# motorController-merged.net
KiCad netlist of a schematic drawn in EAGLE
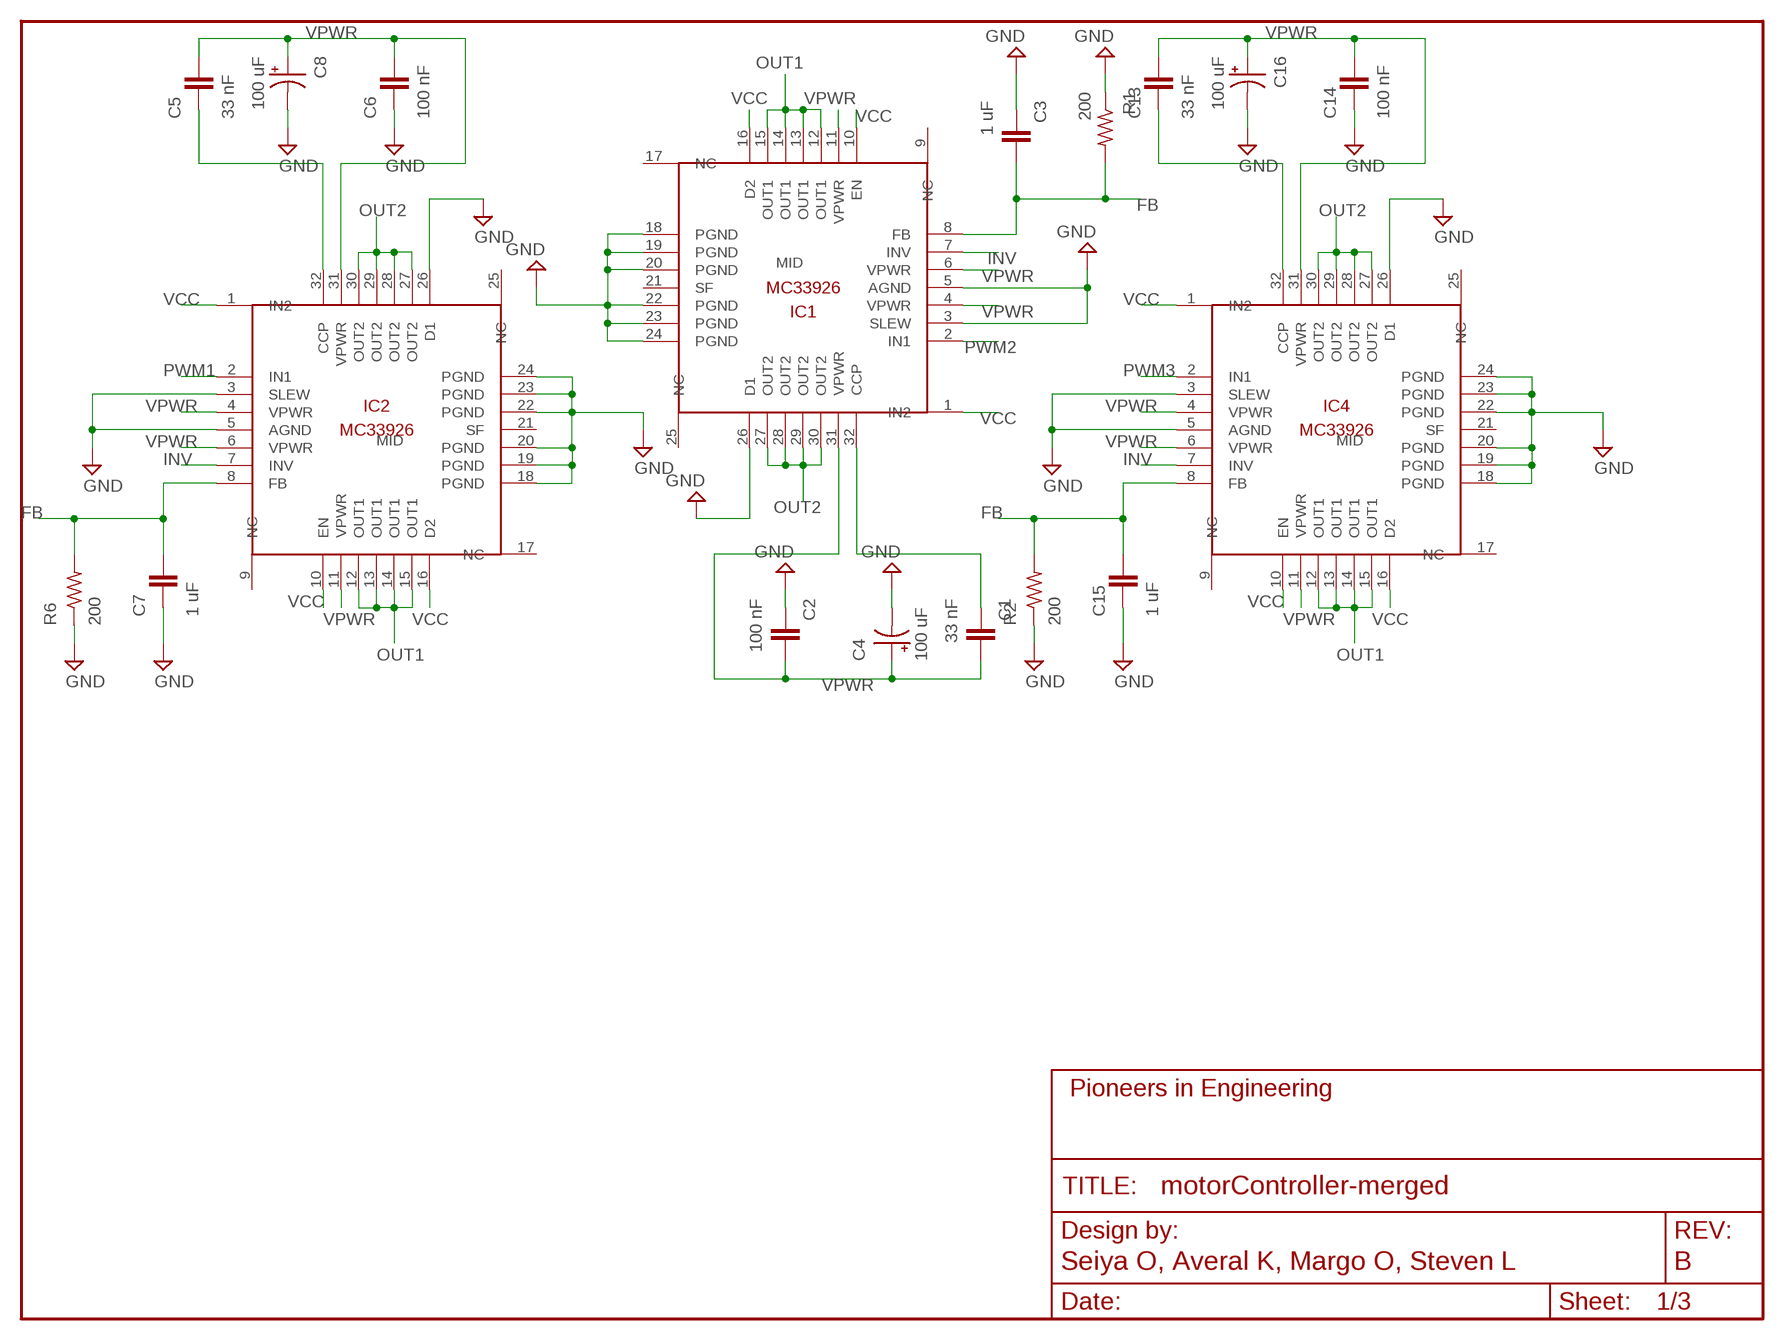
[diagram p0: schematic, sheet 1]
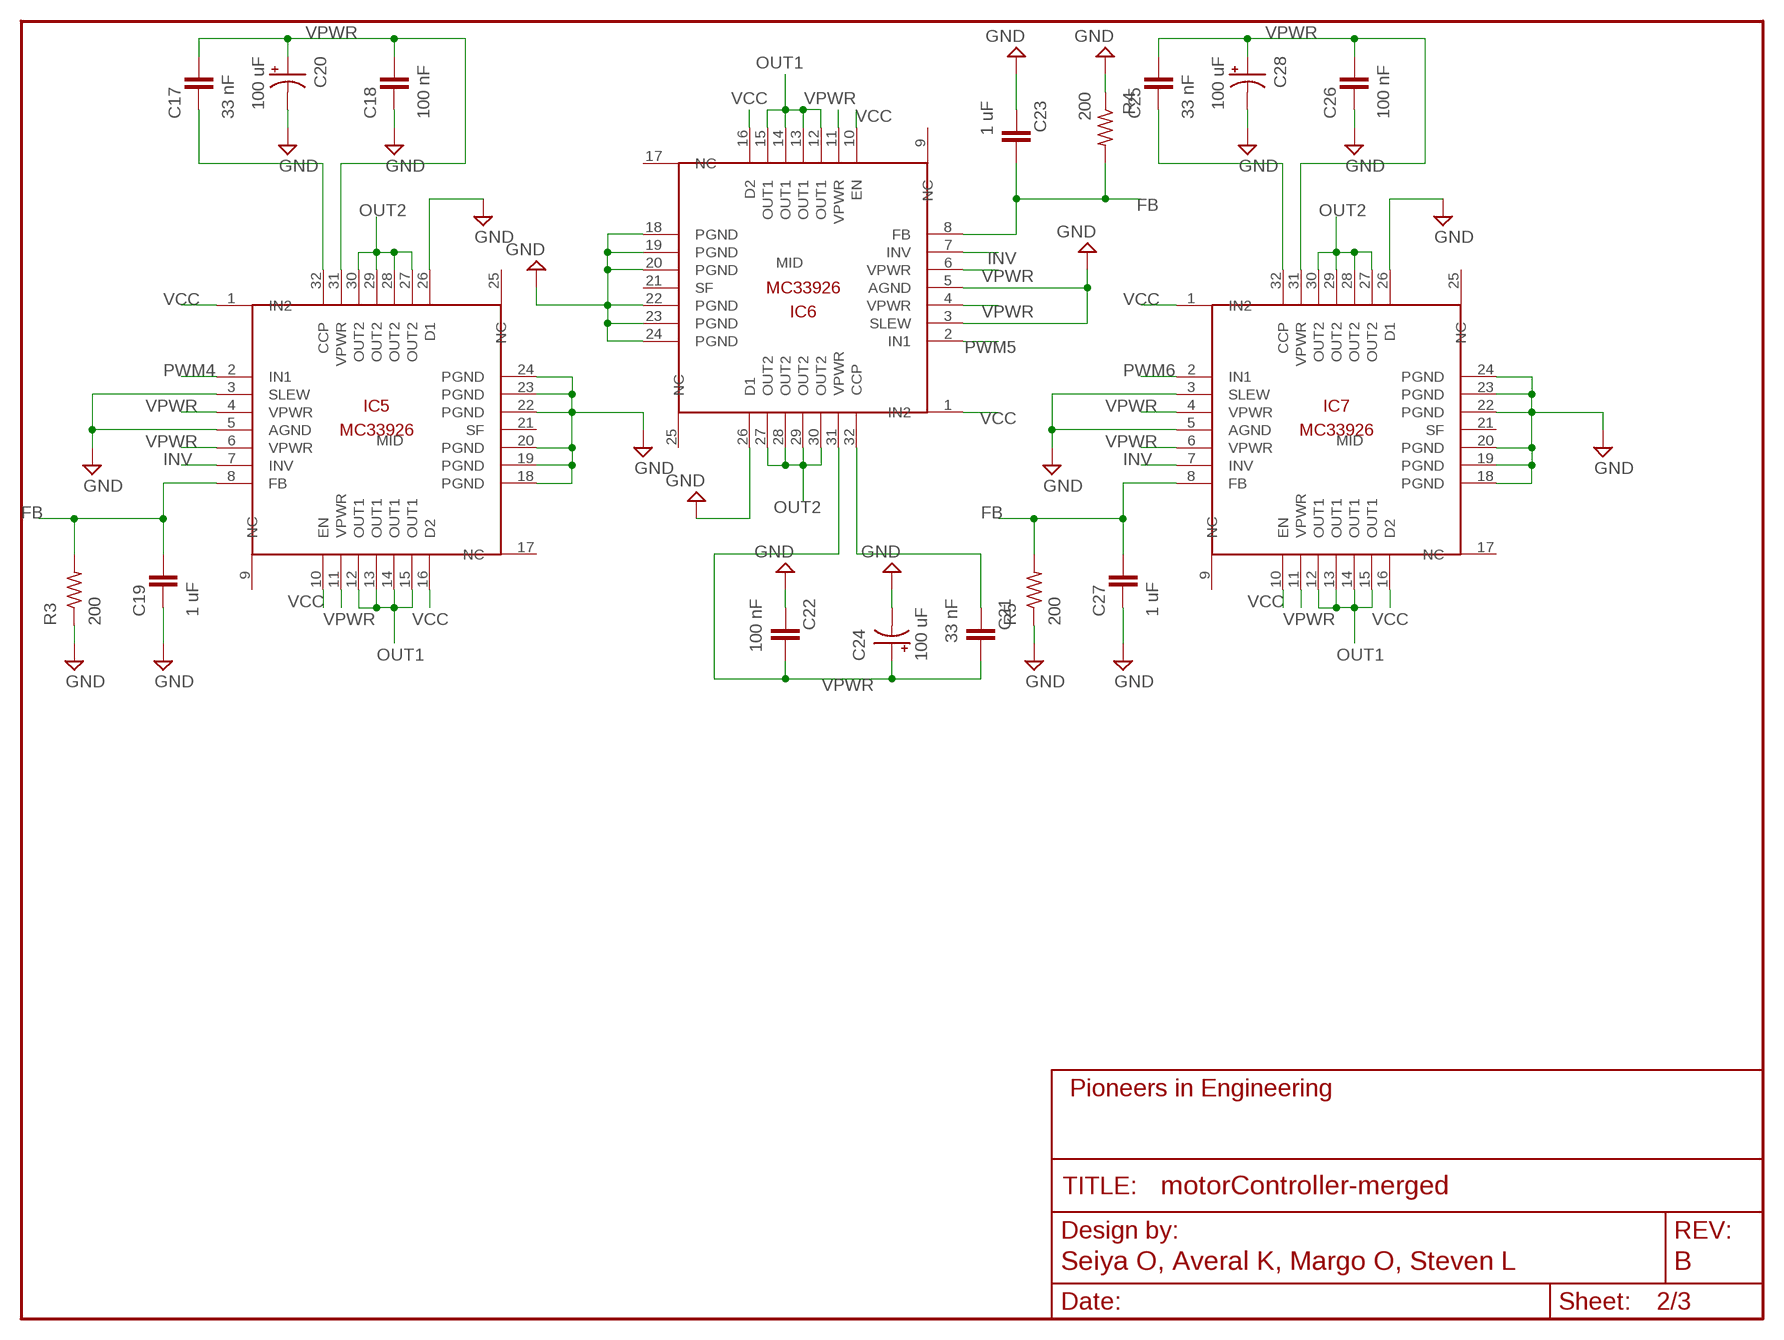
[diagram p1: schematic, sheet 2]
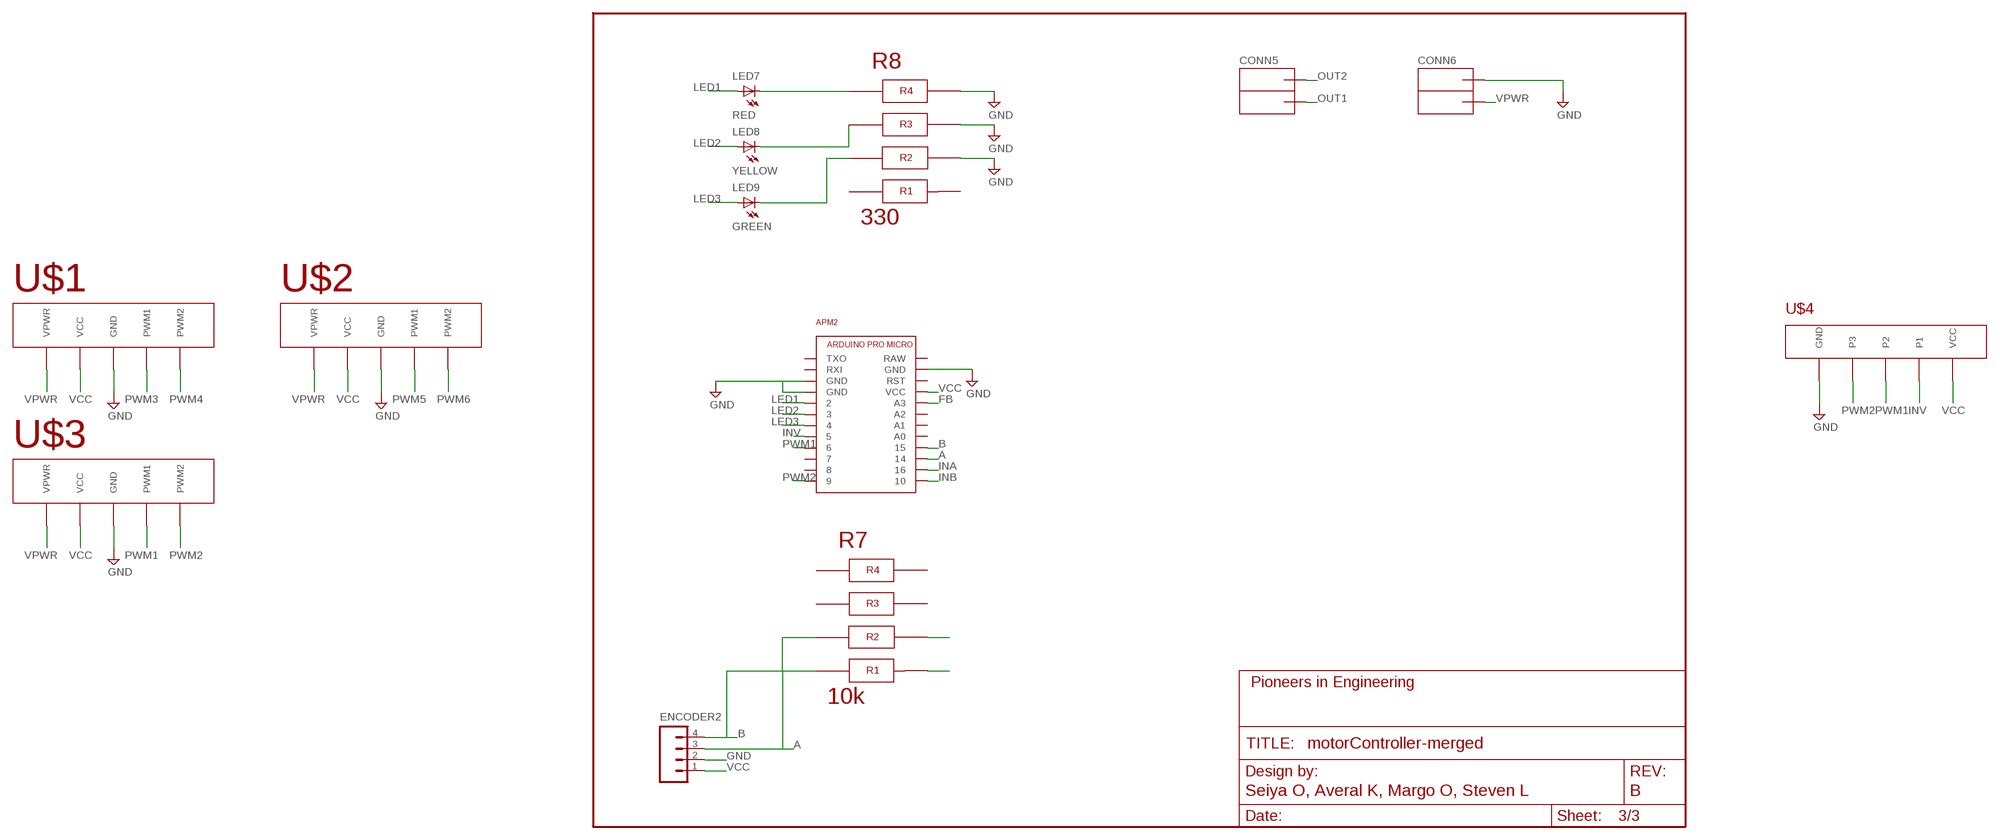
[diagram p2: schematic, sheet 3]

(export (version "E")
  (design (tool "Eeschema 10.0.6"))
  (components
    (comp (ref "C17")
      (value "33 nF")
      (footprint "eagle-import:0603-CAP")
      (libsource (lib "eagle-import") (part "CAP0603-CAP"))
    )
    (comp (ref "C18")
      (value "100 nF")
      (footprint "eagle-import:0603-CAP")
      (libsource (lib "eagle-import") (part "CAP0603-CAP"))
    )
    (comp (ref "C19")
      (value "1 uF")
      (footprint "eagle-import:0603-CAP")
      (libsource (lib "eagle-import") (part "CAP0603-CAP"))
    )
    (comp (ref "C20")
      (value "100 uF")
      (footprint "eagle-import:.248_CAP_THRU")
      (libsource (lib "eagle-import") (part "CAP_POLRADIAL"))
    )
    (comp (ref "C21")
      (value "33 nF")
      (footprint "eagle-import:0603-CAP")
      (libsource (lib "eagle-import") (part "CAP0603-CAP"))
    )
    (comp (ref "C22")
      (value "100 nF")
      (footprint "eagle-import:0603-CAP")
      (libsource (lib "eagle-import") (part "CAP0603-CAP"))
    )
    (comp (ref "C23")
      (value "1 uF")
      (footprint "eagle-import:0603-CAP")
      (libsource (lib "eagle-import") (part "CAP0603-CAP"))
    )
    (comp (ref "C24")
      (value "100 uF")
      (footprint "eagle-import:.248_CAP_THRU")
      (libsource (lib "eagle-import") (part "CAP_POLRADIAL"))
    )
    (comp (ref "C25")
      (value "33 nF")
      (footprint "eagle-import:0603-CAP")
      (libsource (lib "eagle-import") (part "CAP0603-CAP"))
    )
    (comp (ref "C26")
      (value "100 nF")
      (footprint "eagle-import:0603-CAP")
      (libsource (lib "eagle-import") (part "CAP0603-CAP"))
    )
    (comp (ref "C27")
      (value "1 uF")
      (footprint "eagle-import:0603-CAP")
      (libsource (lib "eagle-import") (part "CAP0603-CAP"))
    )
    (comp (ref "C28")
      (value "100 uF")
      (footprint "eagle-import:.248_CAP_THRU")
      (libsource (lib "eagle-import") (part "CAP_POLRADIAL"))
    )
    (comp (ref "IC5")
      (value "MC33926")
      (footprint "eagle-import:PQFN-32")
      (libsource (lib "eagle-import") (part "MC33926"))
    )
    (comp (ref "IC6")
      (value "MC33926")
      (footprint "eagle-import:PQFN-32")
      (libsource (lib "eagle-import") (part "MC33926"))
    )
    (comp (ref "IC7")
      (value "MC33926")
      (footprint "eagle-import:PQFN-32")
      (libsource (lib "eagle-import") (part "MC33926"))
    )
    (comp (ref "R3")
      (value "200")
      (footprint "eagle-import:R0603")
      (fields (field (name "MANUFACTURER") "Rohm Semiconductor"))
      (libsource (lib "eagle-import") (part "R-US_R0603"))
    )
    (comp (ref "R4")
      (value "200")
      (footprint "eagle-import:R0603")
      (fields (field (name "MANUFACTURER") "Rohm Semiconductor"))
      (libsource (lib "eagle-import") (part "R-US_R0603"))
    )
    (comp (ref "R5")
      (value "200")
      (footprint "eagle-import:R0603")
      (fields (field (name "MANUFACTURER") "Rohm Semiconductor"))
      (libsource (lib "eagle-import") (part "R-US_R0603"))
    )
    (comp (ref "APM2")
      (value "ARDUINO_PRO_MICRO")
      (footprint "eagle-import:ARDUINO_PRO_MICRO")
      (fields
        (field (name "DISTRIBUTOR_PART_NUMBER") "32284746884")
        (field (name "MANUFACTURER") "Feiyang electronics")
      )
      (libsource (lib "eagle-import") (part "ARDUINO_PRO_MICRO"))
    )
    (comp (ref "CONN5")
      (value "ANDERSONVERTICAL")
      (footprint "eagle-import:ANDERSON_VERTICAL")
      (libsource (lib "eagle-import") (part "ANDERSONVERTICAL"))
    )
    (comp (ref "CONN6")
      (value "ANDERSONVERTICAL")
      (footprint "eagle-import:ANDERSON_VERTICAL")
      (libsource (lib "eagle-import") (part "ANDERSONVERTICAL"))
    )
    (comp (ref "ENCODER2")
      (value "M041X04-MTA")
      (footprint "eagle-import:1X04-MTA")
      (libsource (lib "eagle-import") (part "M041X04-MTA"))
    )
    (comp (ref "LED7")
      (value "RED")
      (footprint "eagle-import:LED-1206")
      (libsource (lib "eagle-import") (part "LED1206"))
    )
    (comp (ref "LED8")
      (value "YELLOW")
      (footprint "eagle-import:LED-1206")
      (libsource (lib "eagle-import") (part "LED1206"))
    )
    (comp (ref "LED9")
      (value "GREEN")
      (footprint "eagle-import:LED-1206")
      (libsource (lib "eagle-import") (part "LED1206"))
    )
    (comp (ref "R7")
      (value "10k")
      (footprint "eagle-import:4X-0603")
      (libsource (lib "eagle-import") (part "4X-0603"))
    )
    (comp (ref "R8")
      (value "330")
      (footprint "eagle-import:4X-0603")
      (libsource (lib "eagle-import") (part "4X-0603"))
    )
    (comp (ref "U$1")
      (value "5XPOGO")
      (footprint "eagle-import:5XPOGO.40_")
      (libsource (lib "eagle-import") (part "5XPOGO"))
    )
    (comp (ref "U$2")
      (value "5XPOGO")
      (footprint "eagle-import:5XPOGO.40_")
      (libsource (lib "eagle-import") (part "5XPOGO"))
    )
    (comp (ref "U$3")
      (value "5XPOGO")
      (footprint "eagle-import:5XPOGO.40_")
      (libsource (lib "eagle-import") (part "5XPOGO"))
    )
    (comp (ref "U$4")
      (value "5PIN5PIN_MC")
      (footprint "eagle-import:5PIN_MC")
      (libsource (lib "eagle-import") (part "5PIN5PIN_MC"))
    )
    (comp (ref "C1")
      (value "33 nF")
      (footprint "eagle-import:0603-CAP")
      (libsource (lib "eagle-import") (part "CAP0603-CAP"))
    )
    (comp (ref "C2")
      (value "100 nF")
      (footprint "eagle-import:0603-CAP")
      (libsource (lib "eagle-import") (part "CAP0603-CAP"))
    )
    (comp (ref "C3")
      (value "1 uF")
      (footprint "eagle-import:0603-CAP")
      (libsource (lib "eagle-import") (part "CAP0603-CAP"))
    )
    (comp (ref "C4")
      (value "100 uF")
      (footprint "eagle-import:.248_CAP_THRU")
      (libsource (lib "eagle-import") (part "CAP_POLRADIAL"))
    )
    (comp (ref "C5")
      (value "33 nF")
      (footprint "eagle-import:0603-CAP")
      (libsource (lib "eagle-import") (part "CAP0603-CAP"))
    )
    (comp (ref "C6")
      (value "100 nF")
      (footprint "eagle-import:0603-CAP")
      (libsource (lib "eagle-import") (part "CAP0603-CAP"))
    )
    (comp (ref "C7")
      (value "1 uF")
      (footprint "eagle-import:0603-CAP")
      (libsource (lib "eagle-import") (part "CAP0603-CAP"))
    )
    (comp (ref "C8")
      (value "100 uF")
      (footprint "eagle-import:.248_CAP_THRU")
      (libsource (lib "eagle-import") (part "CAP_POLRADIAL"))
    )
    (comp (ref "C13")
      (value "33 nF")
      (footprint "eagle-import:0603-CAP")
      (libsource (lib "eagle-import") (part "CAP0603-CAP"))
    )
    (comp (ref "C14")
      (value "100 nF")
      (footprint "eagle-import:0603-CAP")
      (libsource (lib "eagle-import") (part "CAP0603-CAP"))
    )
    (comp (ref "C15")
      (value "1 uF")
      (footprint "eagle-import:0603-CAP")
      (libsource (lib "eagle-import") (part "CAP0603-CAP"))
    )
    (comp (ref "C16")
      (value "100 uF")
      (footprint "eagle-import:.248_CAP_THRU")
      (libsource (lib "eagle-import") (part "CAP_POLRADIAL"))
    )
    (comp (ref "IC1")
      (value "MC33926")
      (footprint "eagle-import:PQFN-32")
      (libsource (lib "eagle-import") (part "MC33926"))
    )
    (comp (ref "IC2")
      (value "MC33926")
      (footprint "eagle-import:PQFN-32")
      (libsource (lib "eagle-import") (part "MC33926"))
    )
    (comp (ref "IC4")
      (value "MC33926")
      (footprint "eagle-import:PQFN-32")
      (libsource (lib "eagle-import") (part "MC33926"))
    )
    (comp (ref "R1")
      (value "200")
      (footprint "eagle-import:R0603")
      (fields (field (name "MANUFACTURER") "Rohm Semiconductor"))
      (libsource (lib "eagle-import") (part "R-US_R0603"))
    )
    (comp (ref "R2")
      (value "200")
      (footprint "eagle-import:R0603")
      (fields (field (name "MANUFACTURER") "Rohm Semiconductor"))
      (libsource (lib "eagle-import") (part "R-US_R0603"))
    )
    (comp (ref "R6")
      (value "200")
      (footprint "eagle-import:R0603")
      (fields (field (name "MANUFACTURER") "Rohm Semiconductor"))
      (libsource (lib "eagle-import") (part "R-US_R0603"))
    )
  )
  (nets
    (net (code "1") (name "A") (class "Default")
      (node (ref "APM2") (pin "14") (pinfunction "14_14") (pintype "bidirectional"))
      (node (ref "ENCODER2") (pin "3") (pinfunction "3_3") (pintype "passive"))
      (node (ref "R7") (pin "7") (pinfunction "7_7") (pintype "bidirectional"))
    )
    (net (code "2") (name "B") (class "Default")
      (node (ref "APM2") (pin "15") (pinfunction "15_15") (pintype "bidirectional"))
      (node (ref "ENCODER2") (pin "4") (pinfunction "4_4") (pintype "passive"))
      (node (ref "R7") (pin "8") (pinfunction "8_8") (pintype "bidirectional"))
    )
    (net (code "3") (name "FB") (class "Default")
      (node (ref "APM2") (pin "A3") (pinfunction "A3_A3") (pintype "bidirectional"))
      (node (ref "C15") (pin "2") (pinfunction "2_2") (pintype "passive"))
      (node (ref "C19") (pin "2") (pinfunction "2_2") (pintype "passive"))
      (node (ref "C23") (pin "2") (pinfunction "2_2") (pintype "passive"))
      (node (ref "C27") (pin "2") (pinfunction "2_2") (pintype "passive"))
      (node (ref "C3") (pin "2") (pinfunction "2_2") (pintype "passive"))
      (node (ref "C7") (pin "2") (pinfunction "2_2") (pintype "passive"))
      (node (ref "IC1") (pin "8") (pinfunction "FB_8") (pintype "bidirectional"))
      (node (ref "IC2") (pin "8") (pinfunction "FB_8") (pintype "bidirectional"))
      (node (ref "IC4") (pin "8") (pinfunction "FB_8") (pintype "bidirectional"))
      (node (ref "IC5") (pin "8") (pinfunction "FB_8") (pintype "bidirectional"))
      (node (ref "IC6") (pin "8") (pinfunction "FB_8") (pintype "bidirectional"))
      (node (ref "IC7") (pin "8") (pinfunction "FB_8") (pintype "bidirectional"))
      (node (ref "R1") (pin "2") (pinfunction "2_2") (pintype "passive"))
      (node (ref "R2") (pin "2") (pinfunction "2_2") (pintype "passive"))
      (node (ref "R3") (pin "2") (pinfunction "2_2") (pintype "passive"))
      (node (ref "R4") (pin "2") (pinfunction "2_2") (pintype "passive"))
      (node (ref "R5") (pin "2") (pinfunction "2_2") (pintype "passive"))
      (node (ref "R6") (pin "2") (pinfunction "2_2") (pintype "passive"))
    )
    (net (code "4") (name "GND") (class "Default")
      (node (ref "APM2") (pin "GND@0") (pinfunction "GND_GND@0") (pintype "bidirectional"))
      (node (ref "APM2") (pin "GND@1") (pinfunction "GND_GND@1") (pintype "bidirectional"))
      (node (ref "APM2") (pin "GND@2") (pinfunction "GND_GND@2") (pintype "bidirectional"))
      (node (ref "C14") (pin "1") (pinfunction "1_1") (pintype "passive"))
      (node (ref "C15") (pin "1") (pinfunction "1_1") (pintype "passive"))
      (node (ref "C16") (pin "MINUS") (pinfunction "-_MINUS") (pintype "passive"))
      (node (ref "C18") (pin "1") (pinfunction "1_1") (pintype "passive"))
      (node (ref "C19") (pin "1") (pinfunction "1_1") (pintype "passive"))
      (node (ref "C2") (pin "1") (pinfunction "1_1") (pintype "passive"))
      (node (ref "C20") (pin "MINUS") (pinfunction "-_MINUS") (pintype "passive"))
      (node (ref "C22") (pin "1") (pinfunction "1_1") (pintype "passive"))
      (node (ref "C23") (pin "1") (pinfunction "1_1") (pintype "passive"))
      (node (ref "C24") (pin "MINUS") (pinfunction "-_MINUS") (pintype "passive"))
      (node (ref "C26") (pin "1") (pinfunction "1_1") (pintype "passive"))
      (node (ref "C27") (pin "1") (pinfunction "1_1") (pintype "passive"))
      (node (ref "C28") (pin "MINUS") (pinfunction "-_MINUS") (pintype "passive"))
      (node (ref "C3") (pin "1") (pinfunction "1_1") (pintype "passive"))
      (node (ref "C4") (pin "MINUS") (pinfunction "-_MINUS") (pintype "passive"))
      (node (ref "C6") (pin "1") (pinfunction "1_1") (pintype "passive"))
      (node (ref "C7") (pin "1") (pinfunction "1_1") (pintype "passive"))
      (node (ref "C8") (pin "MINUS") (pinfunction "-_MINUS") (pintype "passive"))
      (node (ref "CONN6") (pin "PIN2") (pinfunction "OUTA_PIN2") (pintype "bidirectional"))
      (node (ref "ENCODER2") (pin "2") (pinfunction "2_2") (pintype "passive"))
      (node (ref "IC1") (pin "18") (pinfunction "PGND_18") (pintype "bidirectional"))
      (node (ref "IC1") (pin "19") (pinfunction "PGND_19") (pintype "bidirectional"))
      (node (ref "IC1") (pin "20") (pinfunction "PGND_20") (pintype "bidirectional"))
      (node (ref "IC1") (pin "22") (pinfunction "PGND_22") (pintype "bidirectional"))
      (node (ref "IC1") (pin "23") (pinfunction "PGND_23") (pintype "bidirectional"))
      (node (ref "IC1") (pin "24") (pinfunction "PGND_24") (pintype "bidirectional"))
      (node (ref "IC1") (pin "26") (pinfunction "D1_26") (pintype "bidirectional"))
      (node (ref "IC1") (pin "3") (pinfunction "SLEW_3") (pintype "bidirectional"))
      (node (ref "IC1") (pin "5") (pinfunction "AGND_5") (pintype "bidirectional"))
      (node (ref "IC2") (pin "18") (pinfunction "PGND_18") (pintype "bidirectional"))
      (node (ref "IC2") (pin "19") (pinfunction "PGND_19") (pintype "bidirectional"))
      (node (ref "IC2") (pin "20") (pinfunction "PGND_20") (pintype "bidirectional"))
      (node (ref "IC2") (pin "22") (pinfunction "PGND_22") (pintype "bidirectional"))
      (node (ref "IC2") (pin "23") (pinfunction "PGND_23") (pintype "bidirectional"))
      (node (ref "IC2") (pin "24") (pinfunction "PGND_24") (pintype "bidirectional"))
      (node (ref "IC2") (pin "26") (pinfunction "D1_26") (pintype "bidirectional"))
      (node (ref "IC2") (pin "3") (pinfunction "SLEW_3") (pintype "bidirectional"))
      (node (ref "IC2") (pin "5") (pinfunction "AGND_5") (pintype "bidirectional"))
      (node (ref "IC4") (pin "18") (pinfunction "PGND_18") (pintype "bidirectional"))
      (node (ref "IC4") (pin "19") (pinfunction "PGND_19") (pintype "bidirectional"))
      (node (ref "IC4") (pin "20") (pinfunction "PGND_20") (pintype "bidirectional"))
      (node (ref "IC4") (pin "22") (pinfunction "PGND_22") (pintype "bidirectional"))
      (node (ref "IC4") (pin "23") (pinfunction "PGND_23") (pintype "bidirectional"))
      (node (ref "IC4") (pin "24") (pinfunction "PGND_24") (pintype "bidirectional"))
      (node (ref "IC4") (pin "26") (pinfunction "D1_26") (pintype "bidirectional"))
      (node (ref "IC4") (pin "3") (pinfunction "SLEW_3") (pintype "bidirectional"))
      (node (ref "IC4") (pin "5") (pinfunction "AGND_5") (pintype "bidirectional"))
      (node (ref "IC5") (pin "18") (pinfunction "PGND_18") (pintype "bidirectional"))
      (node (ref "IC5") (pin "19") (pinfunction "PGND_19") (pintype "bidirectional"))
      (node (ref "IC5") (pin "20") (pinfunction "PGND_20") (pintype "bidirectional"))
      (node (ref "IC5") (pin "22") (pinfunction "PGND_22") (pintype "bidirectional"))
      (node (ref "IC5") (pin "23") (pinfunction "PGND_23") (pintype "bidirectional"))
      (node (ref "IC5") (pin "24") (pinfunction "PGND_24") (pintype "bidirectional"))
      (node (ref "IC5") (pin "26") (pinfunction "D1_26") (pintype "bidirectional"))
      (node (ref "IC5") (pin "3") (pinfunction "SLEW_3") (pintype "bidirectional"))
      (node (ref "IC5") (pin "5") (pinfunction "AGND_5") (pintype "bidirectional"))
      (node (ref "IC6") (pin "18") (pinfunction "PGND_18") (pintype "bidirectional"))
      (node (ref "IC6") (pin "19") (pinfunction "PGND_19") (pintype "bidirectional"))
      (node (ref "IC6") (pin "20") (pinfunction "PGND_20") (pintype "bidirectional"))
      (node (ref "IC6") (pin "22") (pinfunction "PGND_22") (pintype "bidirectional"))
      (node (ref "IC6") (pin "23") (pinfunction "PGND_23") (pintype "bidirectional"))
      (node (ref "IC6") (pin "24") (pinfunction "PGND_24") (pintype "bidirectional"))
      (node (ref "IC6") (pin "26") (pinfunction "D1_26") (pintype "bidirectional"))
      (node (ref "IC6") (pin "3") (pinfunction "SLEW_3") (pintype "bidirectional"))
      (node (ref "IC6") (pin "5") (pinfunction "AGND_5") (pintype "bidirectional"))
      (node (ref "IC7") (pin "18") (pinfunction "PGND_18") (pintype "bidirectional"))
      (node (ref "IC7") (pin "19") (pinfunction "PGND_19") (pintype "bidirectional"))
      (node (ref "IC7") (pin "20") (pinfunction "PGND_20") (pintype "bidirectional"))
      (node (ref "IC7") (pin "22") (pinfunction "PGND_22") (pintype "bidirectional"))
      (node (ref "IC7") (pin "23") (pinfunction "PGND_23") (pintype "bidirectional"))
      (node (ref "IC7") (pin "24") (pinfunction "PGND_24") (pintype "bidirectional"))
      (node (ref "IC7") (pin "26") (pinfunction "D1_26") (pintype "bidirectional"))
      (node (ref "IC7") (pin "3") (pinfunction "SLEW_3") (pintype "bidirectional"))
      (node (ref "IC7") (pin "5") (pinfunction "AGND_5") (pintype "bidirectional"))
      (node (ref "R1") (pin "1") (pinfunction "1_1") (pintype "passive"))
      (node (ref "R2") (pin "1") (pinfunction "1_1") (pintype "passive"))
      (node (ref "R3") (pin "1") (pinfunction "1_1") (pintype "passive"))
      (node (ref "R4") (pin "1") (pinfunction "1_1") (pintype "passive"))
      (node (ref "R5") (pin "1") (pinfunction "1_1") (pintype "passive"))
      (node (ref "R6") (pin "1") (pinfunction "1_1") (pintype "passive"))
      (node (ref "R8") (pin "2") (pinfunction "2_2") (pintype "bidirectional"))
      (node (ref "R8") (pin "3") (pinfunction "3_3") (pintype "bidirectional"))
      (node (ref "R8") (pin "4") (pinfunction "4_4") (pintype "bidirectional"))
      (node (ref "U$1") (pin "GND") (pinfunction "GND_GND") (pintype "bidirectional"))
      (node (ref "U$2") (pin "GND") (pinfunction "GND_GND") (pintype "bidirectional"))
      (node (ref "U$3") (pin "GND") (pinfunction "GND_GND") (pintype "bidirectional"))
      (node (ref "U$4") (pin "GND") (pinfunction "GND_GND") (pintype "bidirectional"))
    )
    (net (code "5") (name "INA") (class "Default")
      (node (ref "APM2") (pin "16") (pinfunction "16_16") (pintype "bidirectional"))
    )
    (net (code "6") (name "INB") (class "Default")
      (node (ref "APM2") (pin "10") (pinfunction "10_10") (pintype "bidirectional"))
    )
    (net (code "7") (name "INV") (class "Default")
      (node (ref "APM2") (pin "5") (pinfunction "5_5") (pintype "bidirectional"))
      (node (ref "IC1") (pin "7") (pinfunction "INV_7") (pintype "bidirectional"))
      (node (ref "IC2") (pin "7") (pinfunction "INV_7") (pintype "bidirectional"))
      (node (ref "IC4") (pin "7") (pinfunction "INV_7") (pintype "bidirectional"))
      (node (ref "IC5") (pin "7") (pinfunction "INV_7") (pintype "bidirectional"))
      (node (ref "IC6") (pin "7") (pinfunction "INV_7") (pintype "bidirectional"))
      (node (ref "IC7") (pin "7") (pinfunction "INV_7") (pintype "bidirectional"))
      (node (ref "U$4") (pin "INV") (pinfunction "P1_INV") (pintype "bidirectional"))
    )
    (net (code "8") (name "LED1") (class "Default")
      (node (ref "APM2") (pin "2") (pinfunction "2_2") (pintype "bidirectional"))
      (node (ref "LED7") (pin "A") (pinfunction "A_A") (pintype "passive"))
    )
    (net (code "9") (name "LED2") (class "Default")
      (node (ref "APM2") (pin "3") (pinfunction "3_3") (pintype "bidirectional"))
      (node (ref "LED8") (pin "A") (pinfunction "A_A") (pintype "passive"))
    )
    (net (code "10") (name "LED3") (class "Default")
      (node (ref "APM2") (pin "4") (pinfunction "4_4") (pintype "bidirectional"))
      (node (ref "LED9") (pin "A") (pinfunction "A_A") (pintype "passive"))
    )
    (net (code "11") (name "Net-(IC1-CCP)") (class "Default")
      (node (ref "C1") (pin "1") (pinfunction "1_1") (pintype "passive"))
      (node (ref "IC1") (pin "32") (pinfunction "CCP_32") (pintype "bidirectional"))
    )
    (net (code "12") (name "Net-(IC2-CCP)") (class "Default")
      (node (ref "C5") (pin "1") (pinfunction "1_1") (pintype "passive"))
      (node (ref "IC2") (pin "32") (pinfunction "CCP_32") (pintype "bidirectional"))
    )
    (net (code "13") (name "Net-(IC4-CCP)") (class "Default")
      (node (ref "C13") (pin "1") (pinfunction "1_1") (pintype "passive"))
      (node (ref "IC4") (pin "32") (pinfunction "CCP_32") (pintype "bidirectional"))
    )
    (net (code "14") (name "Net-(IC5-CCP)") (class "Default")
      (node (ref "C17") (pin "1") (pinfunction "1_1") (pintype "passive"))
      (node (ref "IC5") (pin "32") (pinfunction "CCP_32") (pintype "bidirectional"))
    )
    (net (code "15") (name "Net-(IC6-CCP)") (class "Default")
      (node (ref "C21") (pin "1") (pinfunction "1_1") (pintype "passive"))
      (node (ref "IC6") (pin "32") (pinfunction "CCP_32") (pintype "bidirectional"))
    )
    (net (code "16") (name "Net-(IC7-CCP)") (class "Default")
      (node (ref "C25") (pin "1") (pinfunction "1_1") (pintype "passive"))
      (node (ref "IC7") (pin "32") (pinfunction "CCP_32") (pintype "bidirectional"))
    )
    (net (code "17") (name "Net-(LED7-PadC)") (class "Default")
      (node (ref "LED7") (pin "C") (pinfunction "C_C") (pintype "passive"))
      (node (ref "R8") (pin "5") (pinfunction "5_5") (pintype "bidirectional"))
    )
    (net (code "18") (name "Net-(LED8-PadC)") (class "Default")
      (node (ref "LED8") (pin "C") (pinfunction "C_C") (pintype "passive"))
      (node (ref "R8") (pin "6") (pinfunction "6_6") (pintype "bidirectional"))
    )
    (net (code "19") (name "Net-(LED9-PadC)") (class "Default")
      (node (ref "LED9") (pin "C") (pinfunction "C_C") (pintype "passive"))
      (node (ref "R8") (pin "7") (pinfunction "7_7") (pintype "bidirectional"))
    )
    (net (code "20") (name "OUT1") (class "Default")
      (node (ref "CONN5") (pin "PIN1") (pinfunction "OUTB_PIN1") (pintype "bidirectional"))
      (node (ref "IC1") (pin "12") (pinfunction "OUT1_12") (pintype "bidirectional"))
      (node (ref "IC1") (pin "13") (pinfunction "OUT1_13") (pintype "bidirectional"))
      (node (ref "IC1") (pin "14") (pinfunction "OUT1_14") (pintype "bidirectional"))
      (node (ref "IC1") (pin "15") (pinfunction "OUT1_15") (pintype "bidirectional"))
      (node (ref "IC2") (pin "12") (pinfunction "OUT1_12") (pintype "bidirectional"))
      (node (ref "IC2") (pin "13") (pinfunction "OUT1_13") (pintype "bidirectional"))
      (node (ref "IC2") (pin "14") (pinfunction "OUT1_14") (pintype "bidirectional"))
      (node (ref "IC2") (pin "15") (pinfunction "OUT1_15") (pintype "bidirectional"))
      (node (ref "IC4") (pin "12") (pinfunction "OUT1_12") (pintype "bidirectional"))
      (node (ref "IC4") (pin "13") (pinfunction "OUT1_13") (pintype "bidirectional"))
      (node (ref "IC4") (pin "14") (pinfunction "OUT1_14") (pintype "bidirectional"))
      (node (ref "IC4") (pin "15") (pinfunction "OUT1_15") (pintype "bidirectional"))
      (node (ref "IC5") (pin "12") (pinfunction "OUT1_12") (pintype "bidirectional"))
      (node (ref "IC5") (pin "13") (pinfunction "OUT1_13") (pintype "bidirectional"))
      (node (ref "IC5") (pin "14") (pinfunction "OUT1_14") (pintype "bidirectional"))
      (node (ref "IC5") (pin "15") (pinfunction "OUT1_15") (pintype "bidirectional"))
      (node (ref "IC6") (pin "12") (pinfunction "OUT1_12") (pintype "bidirectional"))
      (node (ref "IC6") (pin "13") (pinfunction "OUT1_13") (pintype "bidirectional"))
      (node (ref "IC6") (pin "14") (pinfunction "OUT1_14") (pintype "bidirectional"))
      (node (ref "IC6") (pin "15") (pinfunction "OUT1_15") (pintype "bidirectional"))
      (node (ref "IC7") (pin "12") (pinfunction "OUT1_12") (pintype "bidirectional"))
      (node (ref "IC7") (pin "13") (pinfunction "OUT1_13") (pintype "bidirectional"))
      (node (ref "IC7") (pin "14") (pinfunction "OUT1_14") (pintype "bidirectional"))
      (node (ref "IC7") (pin "15") (pinfunction "OUT1_15") (pintype "bidirectional"))
    )
    (net (code "21") (name "OUT2") (class "Default")
      (node (ref "CONN5") (pin "PIN2") (pinfunction "OUTA_PIN2") (pintype "bidirectional"))
      (node (ref "IC1") (pin "27") (pinfunction "OUT2_27") (pintype "bidirectional"))
      (node (ref "IC1") (pin "28") (pinfunction "OUT2_28") (pintype "bidirectional"))
      (node (ref "IC1") (pin "29") (pinfunction "OUT2_29") (pintype "bidirectional"))
      (node (ref "IC1") (pin "30") (pinfunction "OUT2_30") (pintype "bidirectional"))
      (node (ref "IC2") (pin "27") (pinfunction "OUT2_27") (pintype "bidirectional"))
      (node (ref "IC2") (pin "28") (pinfunction "OUT2_28") (pintype "bidirectional"))
      (node (ref "IC2") (pin "29") (pinfunction "OUT2_29") (pintype "bidirectional"))
      (node (ref "IC2") (pin "30") (pinfunction "OUT2_30") (pintype "bidirectional"))
      (node (ref "IC4") (pin "27") (pinfunction "OUT2_27") (pintype "bidirectional"))
      (node (ref "IC4") (pin "28") (pinfunction "OUT2_28") (pintype "bidirectional"))
      (node (ref "IC4") (pin "29") (pinfunction "OUT2_29") (pintype "bidirectional"))
      (node (ref "IC4") (pin "30") (pinfunction "OUT2_30") (pintype "bidirectional"))
      (node (ref "IC5") (pin "27") (pinfunction "OUT2_27") (pintype "bidirectional"))
      (node (ref "IC5") (pin "28") (pinfunction "OUT2_28") (pintype "bidirectional"))
      (node (ref "IC5") (pin "29") (pinfunction "OUT2_29") (pintype "bidirectional"))
      (node (ref "IC5") (pin "30") (pinfunction "OUT2_30") (pintype "bidirectional"))
      (node (ref "IC6") (pin "27") (pinfunction "OUT2_27") (pintype "bidirectional"))
      (node (ref "IC6") (pin "28") (pinfunction "OUT2_28") (pintype "bidirectional"))
      (node (ref "IC6") (pin "29") (pinfunction "OUT2_29") (pintype "bidirectional"))
      (node (ref "IC6") (pin "30") (pinfunction "OUT2_30") (pintype "bidirectional"))
      (node (ref "IC7") (pin "27") (pinfunction "OUT2_27") (pintype "bidirectional"))
      (node (ref "IC7") (pin "28") (pinfunction "OUT2_28") (pintype "bidirectional"))
      (node (ref "IC7") (pin "29") (pinfunction "OUT2_29") (pintype "bidirectional"))
      (node (ref "IC7") (pin "30") (pinfunction "OUT2_30") (pintype "bidirectional"))
    )
    (net (code "22") (name "PWM1") (class "Default")
      (node (ref "APM2") (pin "6") (pinfunction "6_6") (pintype "bidirectional"))
      (node (ref "IC2") (pin "2") (pinfunction "IN1_2") (pintype "bidirectional"))
      (node (ref "U$3") (pin "PWM1") (pinfunction "PWM1_PWM1") (pintype "bidirectional"))
      (node (ref "U$4") (pin "PWM1") (pinfunction "P2_PWM1") (pintype "bidirectional"))
    )
    (net (code "23") (name "PWM2") (class "Default")
      (node (ref "APM2") (pin "9") (pinfunction "9_9") (pintype "bidirectional"))
      (node (ref "IC1") (pin "2") (pinfunction "IN1_2") (pintype "bidirectional"))
      (node (ref "U$3") (pin "PWM2") (pinfunction "PWM2_PWM2") (pintype "bidirectional"))
      (node (ref "U$4") (pin "PWM2") (pinfunction "P3_PWM2") (pintype "bidirectional"))
    )
    (net (code "24") (name "PWM3") (class "Default")
      (node (ref "IC4") (pin "2") (pinfunction "IN1_2") (pintype "bidirectional"))
      (node (ref "U$1") (pin "PWM1") (pinfunction "PWM1_PWM1") (pintype "bidirectional"))
    )
    (net (code "25") (name "PWM4") (class "Default")
      (node (ref "IC5") (pin "2") (pinfunction "IN1_2") (pintype "bidirectional"))
      (node (ref "U$1") (pin "PWM2") (pinfunction "PWM2_PWM2") (pintype "bidirectional"))
    )
    (net (code "26") (name "PWM5") (class "Default")
      (node (ref "IC6") (pin "2") (pinfunction "IN1_2") (pintype "bidirectional"))
      (node (ref "U$2") (pin "PWM1") (pinfunction "PWM1_PWM1") (pintype "bidirectional"))
    )
    (net (code "27") (name "PWM6") (class "Default")
      (node (ref "IC7") (pin "2") (pinfunction "IN1_2") (pintype "bidirectional"))
      (node (ref "U$2") (pin "PWM2") (pinfunction "PWM2_PWM2") (pintype "bidirectional"))
    )
    (net (code "28") (name "VCC") (class "Default")
      (node (ref "APM2") (pin "VCC") (pinfunction "VCC_VCC") (pintype "bidirectional"))
      (node (ref "ENCODER2") (pin "1") (pinfunction "1_1") (pintype "passive"))
      (node (ref "IC1") (pin "1") (pinfunction "IN2_1") (pintype "bidirectional"))
      (node (ref "IC1") (pin "10") (pinfunction "EN_10") (pintype "bidirectional"))
      (node (ref "IC1") (pin "16") (pinfunction "D2_16") (pintype "bidirectional"))
      (node (ref "IC2") (pin "1") (pinfunction "IN2_1") (pintype "bidirectional"))
      (node (ref "IC2") (pin "10") (pinfunction "EN_10") (pintype "bidirectional"))
      (node (ref "IC2") (pin "16") (pinfunction "D2_16") (pintype "bidirectional"))
      (node (ref "IC4") (pin "1") (pinfunction "IN2_1") (pintype "bidirectional"))
      (node (ref "IC4") (pin "10") (pinfunction "EN_10") (pintype "bidirectional"))
      (node (ref "IC4") (pin "16") (pinfunction "D2_16") (pintype "bidirectional"))
      (node (ref "IC5") (pin "1") (pinfunction "IN2_1") (pintype "bidirectional"))
      (node (ref "IC5") (pin "10") (pinfunction "EN_10") (pintype "bidirectional"))
      (node (ref "IC5") (pin "16") (pinfunction "D2_16") (pintype "bidirectional"))
      (node (ref "IC6") (pin "1") (pinfunction "IN2_1") (pintype "bidirectional"))
      (node (ref "IC6") (pin "10") (pinfunction "EN_10") (pintype "bidirectional"))
      (node (ref "IC6") (pin "16") (pinfunction "D2_16") (pintype "bidirectional"))
      (node (ref "IC7") (pin "1") (pinfunction "IN2_1") (pintype "bidirectional"))
      (node (ref "IC7") (pin "10") (pinfunction "EN_10") (pintype "bidirectional"))
      (node (ref "IC7") (pin "16") (pinfunction "D2_16") (pintype "bidirectional"))
      (node (ref "R7") (pin "1") (pinfunction "1_1") (pintype "bidirectional"))
      (node (ref "R7") (pin "2") (pinfunction "2_2") (pintype "bidirectional"))
      (node (ref "U$1") (pin "VCC") (pinfunction "VCC_VCC") (pintype "bidirectional"))
      (node (ref "U$2") (pin "VCC") (pinfunction "VCC_VCC") (pintype "bidirectional"))
      (node (ref "U$3") (pin "VCC") (pinfunction "VCC_VCC") (pintype "bidirectional"))
      (node (ref "U$4") (pin "VCC") (pinfunction "VCC_VCC") (pintype "bidirectional"))
    )
    (net (code "29") (name "VPWR") (class "Default")
      (node (ref "C1") (pin "2") (pinfunction "2_2") (pintype "passive"))
      (node (ref "C13") (pin "2") (pinfunction "2_2") (pintype "passive"))
      (node (ref "C14") (pin "2") (pinfunction "2_2") (pintype "passive"))
      (node (ref "C16") (pin "PLUS") (pinfunction "+_PLUS") (pintype "passive"))
      (node (ref "C17") (pin "2") (pinfunction "2_2") (pintype "passive"))
      (node (ref "C18") (pin "2") (pinfunction "2_2") (pintype "passive"))
      (node (ref "C2") (pin "2") (pinfunction "2_2") (pintype "passive"))
      (node (ref "C20") (pin "PLUS") (pinfunction "+_PLUS") (pintype "passive"))
      (node (ref "C21") (pin "2") (pinfunction "2_2") (pintype "passive"))
      (node (ref "C22") (pin "2") (pinfunction "2_2") (pintype "passive"))
      (node (ref "C24") (pin "PLUS") (pinfunction "+_PLUS") (pintype "passive"))
      (node (ref "C25") (pin "2") (pinfunction "2_2") (pintype "passive"))
      (node (ref "C26") (pin "2") (pinfunction "2_2") (pintype "passive"))
      (node (ref "C28") (pin "PLUS") (pinfunction "+_PLUS") (pintype "passive"))
      (node (ref "C4") (pin "PLUS") (pinfunction "+_PLUS") (pintype "passive"))
      (node (ref "C5") (pin "2") (pinfunction "2_2") (pintype "passive"))
      (node (ref "C6") (pin "2") (pinfunction "2_2") (pintype "passive"))
      (node (ref "C8") (pin "PLUS") (pinfunction "+_PLUS") (pintype "passive"))
      (node (ref "CONN6") (pin "PIN1") (pinfunction "OUTB_PIN1") (pintype "bidirectional"))
      (node (ref "IC1") (pin "11") (pinfunction "VPWR_11") (pintype "bidirectional"))
      (node (ref "IC1") (pin "31") (pinfunction "VPWR_31") (pintype "bidirectional"))
      (node (ref "IC1") (pin "4") (pinfunction "VPWR_4") (pintype "bidirectional"))
      (node (ref "IC1") (pin "6") (pinfunction "VPWR_6") (pintype "bidirectional"))
      (node (ref "IC2") (pin "11") (pinfunction "VPWR_11") (pintype "bidirectional"))
      (node (ref "IC2") (pin "31") (pinfunction "VPWR_31") (pintype "bidirectional"))
      (node (ref "IC2") (pin "4") (pinfunction "VPWR_4") (pintype "bidirectional"))
      (node (ref "IC2") (pin "6") (pinfunction "VPWR_6") (pintype "bidirectional"))
      (node (ref "IC4") (pin "11") (pinfunction "VPWR_11") (pintype "bidirectional"))
      (node (ref "IC4") (pin "31") (pinfunction "VPWR_31") (pintype "bidirectional"))
      (node (ref "IC4") (pin "4") (pinfunction "VPWR_4") (pintype "bidirectional"))
      (node (ref "IC4") (pin "6") (pinfunction "VPWR_6") (pintype "bidirectional"))
      (node (ref "IC5") (pin "11") (pinfunction "VPWR_11") (pintype "bidirectional"))
      (node (ref "IC5") (pin "31") (pinfunction "VPWR_31") (pintype "bidirectional"))
      (node (ref "IC5") (pin "4") (pinfunction "VPWR_4") (pintype "bidirectional"))
      (node (ref "IC5") (pin "6") (pinfunction "VPWR_6") (pintype "bidirectional"))
      (node (ref "IC6") (pin "11") (pinfunction "VPWR_11") (pintype "bidirectional"))
      (node (ref "IC6") (pin "31") (pinfunction "VPWR_31") (pintype "bidirectional"))
      (node (ref "IC6") (pin "4") (pinfunction "VPWR_4") (pintype "bidirectional"))
      (node (ref "IC6") (pin "6") (pinfunction "VPWR_6") (pintype "bidirectional"))
      (node (ref "IC7") (pin "11") (pinfunction "VPWR_11") (pintype "bidirectional"))
      (node (ref "IC7") (pin "31") (pinfunction "VPWR_31") (pintype "bidirectional"))
      (node (ref "IC7") (pin "4") (pinfunction "VPWR_4") (pintype "bidirectional"))
      (node (ref "IC7") (pin "6") (pinfunction "VPWR_6") (pintype "bidirectional"))
      (node (ref "U$1") (pin "VPWR") (pinfunction "VPWR_VPWR") (pintype "bidirectional"))
      (node (ref "U$2") (pin "VPWR") (pinfunction "VPWR_VPWR") (pintype "bidirectional"))
      (node (ref "U$3") (pin "VPWR") (pinfunction "VPWR_VPWR") (pintype "bidirectional"))
    )
    (net (code "30") (name "unconnected-(APM2-Pad7)") (class "Default")
      (node (ref "APM2") (pin "7") (pinfunction "7_7") (pintype "bidirectional"))
    )
    (net (code "31") (name "unconnected-(APM2-Pad8)") (class "Default")
      (node (ref "APM2") (pin "8") (pinfunction "8_8") (pintype "bidirectional"))
    )
    (net (code "32") (name "unconnected-(APM2-PadA0)") (class "Default")
      (node (ref "APM2") (pin "A0") (pinfunction "A0_A0") (pintype "bidirectional"))
    )
    (net (code "33") (name "unconnected-(APM2-PadA1)") (class "Default")
      (node (ref "APM2") (pin "A1") (pinfunction "A1_A1") (pintype "bidirectional"))
    )
    (net (code "34") (name "unconnected-(APM2-PadA2)") (class "Default")
      (node (ref "APM2") (pin "A2") (pinfunction "A2_A2") (pintype "bidirectional"))
    )
    (net (code "35") (name "unconnected-(APM2-PadRAW)") (class "Default")
      (node (ref "APM2") (pin "RAW") (pinfunction "RAW_RAW") (pintype "bidirectional"))
    )
    (net (code "36") (name "unconnected-(APM2-PadRST)") (class "Default")
      (node (ref "APM2") (pin "RST") (pinfunction "RST_RST") (pintype "bidirectional"))
    )
    (net (code "37") (name "unconnected-(APM2-PadRXI)") (class "Default")
      (node (ref "APM2") (pin "RXI") (pinfunction "RXI_RXI") (pintype "bidirectional"))
    )
    (net (code "38") (name "unconnected-(APM2-PadTXO)") (class "Default")
      (node (ref "APM2") (pin "TXO") (pinfunction "TXO_TXO") (pintype "bidirectional"))
    )
    (net (code "39") (name "unconnected-(IC1-AGND-PadMID)") (class "Default")
      (node (ref "IC1") (pin "MID") (pinfunction "AGND_MID") (pintype "bidirectional"))
    )
    (net (code "40") (name "unconnected-(IC1-NC-Pad9)") (class "Default")
      (node (ref "IC1") (pin "9") (pinfunction "NC_9") (pintype "bidirectional"))
    )
    (net (code "41") (name "unconnected-(IC1-NC-Pad17)") (class "Default")
      (node (ref "IC1") (pin "17") (pinfunction "NC_17") (pintype "bidirectional"))
    )
    (net (code "42") (name "unconnected-(IC1-NC-Pad25)") (class "Default")
      (node (ref "IC1") (pin "25") (pinfunction "NC_25") (pintype "bidirectional"))
    )
    (net (code "43") (name "unconnected-(IC1-SF-Pad21)") (class "Default")
      (node (ref "IC1") (pin "21") (pinfunction "SF_21") (pintype "bidirectional"))
    )
    (net (code "44") (name "unconnected-(IC2-AGND-PadMID)") (class "Default")
      (node (ref "IC2") (pin "MID") (pinfunction "AGND_MID") (pintype "bidirectional"))
    )
    (net (code "45") (name "unconnected-(IC2-NC-Pad9)") (class "Default")
      (node (ref "IC2") (pin "9") (pinfunction "NC_9") (pintype "bidirectional"))
    )
    (net (code "46") (name "unconnected-(IC2-NC-Pad17)") (class "Default")
      (node (ref "IC2") (pin "17") (pinfunction "NC_17") (pintype "bidirectional"))
    )
    (net (code "47") (name "unconnected-(IC2-NC-Pad25)") (class "Default")
      (node (ref "IC2") (pin "25") (pinfunction "NC_25") (pintype "bidirectional"))
    )
    (net (code "48") (name "unconnected-(IC2-SF-Pad21)") (class "Default")
      (node (ref "IC2") (pin "21") (pinfunction "SF_21") (pintype "bidirectional"))
    )
    (net (code "49") (name "unconnected-(IC4-AGND-PadMID)") (class "Default")
      (node (ref "IC4") (pin "MID") (pinfunction "AGND_MID") (pintype "bidirectional"))
    )
    (net (code "50") (name "unconnected-(IC4-NC-Pad9)") (class "Default")
      (node (ref "IC4") (pin "9") (pinfunction "NC_9") (pintype "bidirectional"))
    )
    (net (code "51") (name "unconnected-(IC4-NC-Pad17)") (class "Default")
      (node (ref "IC4") (pin "17") (pinfunction "NC_17") (pintype "bidirectional"))
    )
    (net (code "52") (name "unconnected-(IC4-NC-Pad25)") (class "Default")
      (node (ref "IC4") (pin "25") (pinfunction "NC_25") (pintype "bidirectional"))
    )
    (net (code "53") (name "unconnected-(IC4-SF-Pad21)") (class "Default")
      (node (ref "IC4") (pin "21") (pinfunction "SF_21") (pintype "bidirectional"))
    )
    (net (code "54") (name "unconnected-(IC5-AGND-PadMID)") (class "Default")
      (node (ref "IC5") (pin "MID") (pinfunction "AGND_MID") (pintype "bidirectional"))
    )
    (net (code "55") (name "unconnected-(IC5-NC-Pad9)") (class "Default")
      (node (ref "IC5") (pin "9") (pinfunction "NC_9") (pintype "bidirectional"))
    )
    (net (code "56") (name "unconnected-(IC5-NC-Pad17)") (class "Default")
      (node (ref "IC5") (pin "17") (pinfunction "NC_17") (pintype "bidirectional"))
    )
    (net (code "57") (name "unconnected-(IC5-NC-Pad25)") (class "Default")
      (node (ref "IC5") (pin "25") (pinfunction "NC_25") (pintype "bidirectional"))
    )
    (net (code "58") (name "unconnected-(IC5-SF-Pad21)") (class "Default")
      (node (ref "IC5") (pin "21") (pinfunction "SF_21") (pintype "bidirectional"))
    )
    (net (code "59") (name "unconnected-(IC6-AGND-PadMID)") (class "Default")
      (node (ref "IC6") (pin "MID") (pinfunction "AGND_MID") (pintype "bidirectional"))
    )
    (net (code "60") (name "unconnected-(IC6-NC-Pad9)") (class "Default")
      (node (ref "IC6") (pin "9") (pinfunction "NC_9") (pintype "bidirectional"))
    )
    (net (code "61") (name "unconnected-(IC6-NC-Pad17)") (class "Default")
      (node (ref "IC6") (pin "17") (pinfunction "NC_17") (pintype "bidirectional"))
    )
    (net (code "62") (name "unconnected-(IC6-NC-Pad25)") (class "Default")
      (node (ref "IC6") (pin "25") (pinfunction "NC_25") (pintype "bidirectional"))
    )
    (net (code "63") (name "unconnected-(IC6-SF-Pad21)") (class "Default")
      (node (ref "IC6") (pin "21") (pinfunction "SF_21") (pintype "bidirectional"))
    )
    (net (code "64") (name "unconnected-(IC7-AGND-PadMID)") (class "Default")
      (node (ref "IC7") (pin "MID") (pinfunction "AGND_MID") (pintype "bidirectional"))
    )
    (net (code "65") (name "unconnected-(IC7-NC-Pad9)") (class "Default")
      (node (ref "IC7") (pin "9") (pinfunction "NC_9") (pintype "bidirectional"))
    )
    (net (code "66") (name "unconnected-(IC7-NC-Pad17)") (class "Default")
      (node (ref "IC7") (pin "17") (pinfunction "NC_17") (pintype "bidirectional"))
    )
    (net (code "67") (name "unconnected-(IC7-NC-Pad25)") (class "Default")
      (node (ref "IC7") (pin "25") (pinfunction "NC_25") (pintype "bidirectional"))
    )
    (net (code "68") (name "unconnected-(IC7-SF-Pad21)") (class "Default")
      (node (ref "IC7") (pin "21") (pinfunction "SF_21") (pintype "bidirectional"))
    )
    (net (code "69") (name "unconnected-(R7-Pad3)") (class "Default")
      (node (ref "R7") (pin "3") (pinfunction "3_3") (pintype "bidirectional"))
    )
    (net (code "70") (name "unconnected-(R7-Pad4)") (class "Default")
      (node (ref "R7") (pin "4") (pinfunction "4_4") (pintype "bidirectional"))
    )
    (net (code "71") (name "unconnected-(R7-Pad5)") (class "Default")
      (node (ref "R7") (pin "5") (pinfunction "5_5") (pintype "bidirectional"))
    )
    (net (code "72") (name "unconnected-(R7-Pad6)") (class "Default")
      (node (ref "R7") (pin "6") (pinfunction "6_6") (pintype "bidirectional"))
    )
    (net (code "73") (name "unconnected-(R8-Pad1)") (class "Default")
      (node (ref "R8") (pin "1") (pinfunction "1_1") (pintype "bidirectional"))
    )
    (net (code "74") (name "unconnected-(R8-Pad8)") (class "Default")
      (node (ref "R8") (pin "8") (pinfunction "8_8") (pintype "bidirectional"))
    )
  )
)
